# WikiPower.net
KiCad netlist of a schematic drawn in Altium Designer
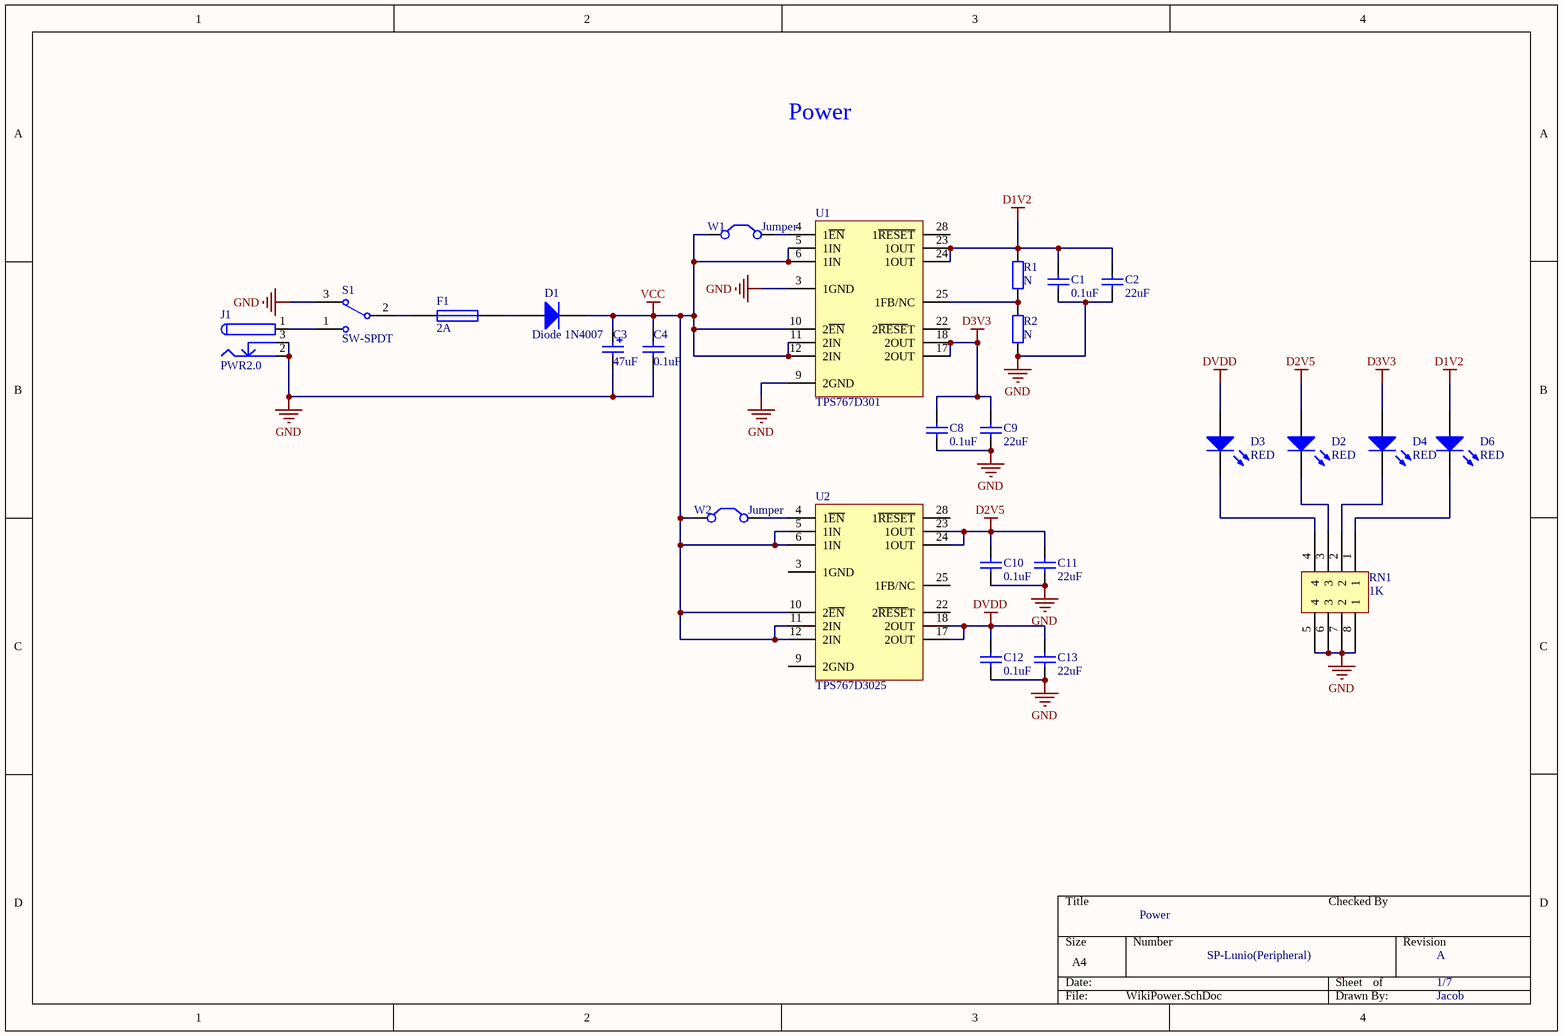
[diagram p0: WikiPower.SchDoc]

(export (version "E")
  (design (tool "Eeschema 10.0.6"))
  (components
    (comp (ref "C1")
      (value "0.1uF")
      (footprint "0603M")
      (description "Capacitor")
      (fields (field (name "PUBLISHER") "Altium Limited"))
      (libsource (lib "Miscellaneous Devices") (part "Cap"))
    )
    (comp (ref "C2")
      (value "22uF")
      (footprint "0805M")
      (description "Capacitor")
      (fields (field (name "PUBLISHER") "Altium Limited"))
      (libsource (lib "Miscellaneous Devices") (part "Cap"))
    )
    (comp (ref "C3")
      (value "47uF")
      (footprint "TAJ-A")
      (description "Polarized Capacitor (Radial)")
      (fields (field (name "PUBLISHER") "Altium Limited"))
      (libsource (lib "Studio") (part "Cap Pol1"))
    )
    (comp (ref "C4")
      (value "0.1uF")
      (footprint "0603M")
      (description "Capacitor")
      (fields (field (name "PUBLISHER") "Altium Limited"))
      (libsource (lib "Miscellaneous Devices") (part "Cap"))
    )
    (comp (ref "C8")
      (value "0.1uF")
      (footprint "0603M")
      (description "Capacitor")
      (fields (field (name "PUBLISHER") "Altium Limited"))
      (libsource (lib "Miscellaneous Devices") (part "Cap"))
    )
    (comp (ref "C9")
      (value "22uF")
      (footprint "0805M")
      (description "Capacitor")
      (fields (field (name "PUBLISHER") "Altium Limited"))
      (libsource (lib "Miscellaneous Devices") (part "Cap"))
    )
    (comp (ref "C10")
      (value "0.1uF")
      (footprint "0603M")
      (description "Capacitor")
      (fields (field (name "PUBLISHER") "Altium Limited"))
      (libsource (lib "Miscellaneous Devices") (part "Cap"))
    )
    (comp (ref "C11")
      (value "22uF")
      (footprint "0805M")
      (description "Capacitor")
      (fields (field (name "PUBLISHER") "Altium Limited"))
      (libsource (lib "Miscellaneous Devices") (part "Cap"))
    )
    (comp (ref "C12")
      (value "0.1uF")
      (footprint "0603M")
      (description "Capacitor")
      (fields (field (name "PUBLISHER") "Altium Limited"))
      (libsource (lib "Miscellaneous Devices") (part "Cap"))
    )
    (comp (ref "C13")
      (value "22uF")
      (footprint "0805M")
      (description "Capacitor")
      (fields (field (name "PUBLISHER") "Altium Limited"))
      (libsource (lib "Miscellaneous Devices") (part "Cap"))
    )
    (comp (ref "D1")
      (value "Diode 1N4007")
      (footprint "1210")
      (description "1 Amp General Purpose Rectifier")
      (fields (field (name "PUBLISHER") "Altium Limited"))
      (libsource (lib "Studio") (part "Diode 1N4007"))
    )
    (comp (ref "D2")
      (value "RED")
      (footprint "0603pn")
      (description "Typical INFRARED GaAs LED")
      (fields (field (name "PUBLISHER") "Altium Limited"))
      (libsource (lib "Miscellaneous Devices") (part "LED0"))
    )
    (comp (ref "D3")
      (value "RED")
      (footprint "0603pn")
      (description "Typical INFRARED GaAs LED")
      (fields (field (name "PUBLISHER") "Altium Limited"))
      (libsource (lib "Miscellaneous Devices") (part "LED0"))
    )
    (comp (ref "D4")
      (value "RED")
      (footprint "0603pn")
      (description "Typical INFRARED GaAs LED")
      (fields (field (name "PUBLISHER") "Altium Limited"))
      (libsource (lib "Miscellaneous Devices") (part "LED0"))
    )
    (comp (ref "D6")
      (value "RED")
      (footprint "0603pn")
      (description "Typical INFRARED GaAs LED")
      (fields (field (name "PUBLISHER") "Altium Limited"))
      (libsource (lib "Miscellaneous Devices") (part "LED0"))
    )
    (comp (ref "F1")
      (value "2A")
      (footprint "1210")
      (description "Fuse")
      (fields (field (name "PUBLISHER") "Altium Limited"))
      (libsource (lib "Studio") (part "Fuse 1"))
    )
    (comp (ref "J1")
      (value "PWR2.0")
      (footprint "PWR JACK 2.0MM")
      (description "Low Voltage Power Supply Connector")
      (fields (field (name "PUBLISHER") "Altium Limited"))
      (libsource (lib "Studio") (part "PWR2.5"))
    )
    (comp (ref "R1")
      (value "N")
      (footprint "0603M")
      (description "Resistor")
      (fields (field (name "PUBLISHER") "Altium Limited"))
      (libsource (lib "Miscellaneous Devices") (part "Res2"))
    )
    (comp (ref "R2")
      (value "N")
      (footprint "0603M")
      (description "Resistor")
      (fields (field (name "PUBLISHER") "Altium Limited"))
      (libsource (lib "Miscellaneous Devices") (part "Res2"))
    )
    (comp (ref "RN1")
      (value "1K")
      (footprint "RN1X4/0603")
      (description "Res Pack 2X4")
      (libsource (lib "Studio") (part "Res Pack 2X4"))
    )
    (comp (ref "S1")
      (value "SW-SPDT")
      (footprint "SK12D07VG3")
      (description "SPDT Subminiature Toggle Switch, Right Angle Mounting, Vertical Actuation")
      (fields (field (name "PUBLISHER") "Altium Limited"))
      (libsource (lib "Miscellaneous Devices") (part "SW-SPDT"))
    )
    (comp (ref "U1")
      (value "TPS767D301")
      (footprint "HTSSOP")
      (description "DOUBLE OUTPUT")
      (libsource (lib "Lunio") (part "TPS757D301"))
    )
    (comp (ref "U2")
      (value "TPS767D3025")
      (footprint "HTSSOP")
      (description "DUAL-OUTPUT LOW-DROPOUT VOLTAGE REGULATORS")
      (libsource (lib "Studio") (part "TPS757D3XX"))
    )
    (comp (ref "W1")
      (value "Jumper")
      (footprint "HDR1X2/2.00MM")
      (description "Jumper Wire")
      (fields (field (name "PUBLISHER") "Altium Limited"))
      (libsource (lib "Miscellaneous Devices") (part "Jumper"))
    )
    (comp (ref "W2")
      (value "Jumper")
      (footprint "HDR1X2/2.00MM")
      (description "Jumper Wire")
      (fields (field (name "PUBLISHER") "Altium Limited"))
      (libsource (lib "Miscellaneous Devices") (part "Jumper"))
    )
  )
  (nets
    (net (code "1") (name "D1V2") (class "Default")
      (node (ref "C1") (pin "2") (pinfunction "2_2") (pintype "passive"))
      (node (ref "C2") (pin "2") (pinfunction "2_2") (pintype "passive"))
      (node (ref "D6") (pin "1") (pinfunction "A_1") (pintype "passive"))
      (node (ref "R1") (pin "2") (pinfunction "2_2") (pintype "passive"))
      (node (ref "U1") (pin "23") (pinfunction "1OUT_23") (pintype "power_in"))
      (node (ref "U1") (pin "24") (pinfunction "1OUT_24") (pintype "power_in"))
    )
    (net (code "2") (name "D2V5") (class "Default")
      (node (ref "C10") (pin "2") (pinfunction "2_2") (pintype "passive"))
      (node (ref "C11") (pin "2") (pinfunction "2_2") (pintype "passive"))
      (node (ref "D2") (pin "1") (pinfunction "A_1") (pintype "passive"))
      (node (ref "U2") (pin "23") (pinfunction "1OUT_23") (pintype "power_in"))
      (node (ref "U2") (pin "24") (pinfunction "1OUT_24") (pintype "power_in"))
    )
    (net (code "3") (name "D3V3") (class "Default")
      (node (ref "C8") (pin "2") (pinfunction "2_2") (pintype "passive"))
      (node (ref "C9") (pin "2") (pinfunction "2_2") (pintype "passive"))
      (node (ref "D4") (pin "1") (pinfunction "A_1") (pintype "passive"))
      (node (ref "U1") (pin "17") (pinfunction "2OUT_17") (pintype "power_in"))
      (node (ref "U1") (pin "18") (pinfunction "2OUT_18") (pintype "power_in"))
    )
    (net (code "4") (name "DVDD") (class "Default")
      (node (ref "C12") (pin "2") (pinfunction "2_2") (pintype "passive"))
      (node (ref "C13") (pin "2") (pinfunction "2_2") (pintype "passive"))
      (node (ref "D3") (pin "1") (pinfunction "A_1") (pintype "passive"))
      (node (ref "U2") (pin "17") (pinfunction "2OUT_17") (pintype "power_in"))
      (node (ref "U2") (pin "18") (pinfunction "2OUT_18") (pintype "power_in"))
    )
    (net (code "5") (name "GND") (class "Default")
      (node (ref "C1") (pin "1") (pinfunction "1_1") (pintype "passive"))
      (node (ref "C10") (pin "1") (pinfunction "1_1") (pintype "passive"))
      (node (ref "C11") (pin "1") (pinfunction "1_1") (pintype "passive"))
      (node (ref "C12") (pin "1") (pinfunction "1_1") (pintype "passive"))
      (node (ref "C13") (pin "1") (pinfunction "1_1") (pintype "passive"))
      (node (ref "C2") (pin "1") (pinfunction "1_1") (pintype "passive"))
      (node (ref "C3") (pin "2") (pinfunction "2_2") (pintype "passive"))
      (node (ref "C4") (pin "1") (pinfunction "1_1") (pintype "passive"))
      (node (ref "C8") (pin "1") (pinfunction "1_1") (pintype "passive"))
      (node (ref "C9") (pin "1") (pinfunction "1_1") (pintype "passive"))
      (node (ref "J1") (pin "2") (pinfunction "2_2") (pintype "power_in"))
      (node (ref "J1") (pin "3") (pinfunction "3_3") (pintype "power_in"))
      (node (ref "R2") (pin "1") (pinfunction "1_1") (pintype "passive"))
      (node (ref "RN1") (pin "5") (pinfunction "4_5") (pintype "passive"))
      (node (ref "RN1") (pin "6") (pinfunction "3_6") (pintype "passive"))
      (node (ref "RN1") (pin "7") (pinfunction "2_7") (pintype "passive"))
      (node (ref "RN1") (pin "8") (pinfunction "1_8") (pintype "passive"))
      (node (ref "S1") (pin "3") (pinfunction "3_3") (pintype "passive"))
      (node (ref "U1") (pin "3") (pinfunction "1GND_3") (pintype "power_in"))
      (node (ref "U1") (pin "9") (pinfunction "2GND_9") (pintype "power_in"))
    )
    (net (code "6") (name "Net-(D1-A)") (class "Default")
      (node (ref "D1") (pin "1") (pinfunction "A_1") (pintype "passive"))
      (node (ref "F1") (pin "2") (pinfunction "2_2") (pintype "passive"))
    )
    (net (code "7") (name "Net-(D2-K)") (class "Default")
      (node (ref "D2") (pin "2") (pinfunction "K_2") (pintype "passive"))
      (node (ref "RN1") (pin "3") (pinfunction "3_3") (pintype "passive"))
    )
    (net (code "8") (name "Net-(D3-K)") (class "Default")
      (node (ref "D3") (pin "2") (pinfunction "K_2") (pintype "passive"))
      (node (ref "RN1") (pin "4") (pinfunction "4_4") (pintype "passive"))
    )
    (net (code "9") (name "Net-(D4-K)") (class "Default")
      (node (ref "D4") (pin "2") (pinfunction "K_2") (pintype "passive"))
      (node (ref "RN1") (pin "2") (pinfunction "2_2") (pintype "passive"))
    )
    (net (code "10") (name "Net-(D6-K)") (class "Default")
      (node (ref "D6") (pin "2") (pinfunction "K_2") (pintype "passive"))
      (node (ref "RN1") (pin "1") (pinfunction "1_1") (pintype "passive"))
    )
    (net (code "11") (name "Net-(F1-Pad1)") (class "Default")
      (node (ref "F1") (pin "1") (pinfunction "1_1") (pintype "passive"))
      (node (ref "S1") (pin "2") (pinfunction "2_2") (pintype "passive"))
    )
    (net (code "12") (name "Net-(J1-Pad1)") (class "Default")
      (node (ref "J1") (pin "1") (pinfunction "1_1") (pintype "power_in"))
      (node (ref "S1") (pin "1") (pinfunction "1_1") (pintype "passive"))
    )
    (net (code "13") (name "Net-(U1-1FB{slash}NC)") (class "Default")
      (node (ref "R1") (pin "1") (pinfunction "1_1") (pintype "passive"))
      (node (ref "R2") (pin "2") (pinfunction "2_2") (pintype "passive"))
      (node (ref "U1") (pin "25") (pinfunction "1FB/NC_25") (pintype "power_in"))
    )
    (net (code "14") (name "Net-(U1-1~{EN})") (class "Default")
      (node (ref "U1") (pin "4") (pinfunction "1~{EN}_4") (pintype "power_in"))
      (node (ref "W1") (pin "2") (pinfunction "C2_2") (pintype "passive"))
    )
    (net (code "15") (name "Net-(U2-1~{EN})") (class "Default")
      (node (ref "U2") (pin "4") (pinfunction "1~{EN}_4") (pintype "power_in"))
      (node (ref "W2") (pin "2") (pinfunction "C2_2") (pintype "passive"))
    )
    (net (code "16") (name "VCC") (class "Default")
      (node (ref "C3") (pin "1") (pinfunction "1_1") (pintype "passive"))
      (node (ref "C4") (pin "2") (pinfunction "2_2") (pintype "passive"))
      (node (ref "D1") (pin "2") (pinfunction "K_2") (pintype "passive"))
      (node (ref "U1") (pin "10") (pinfunction "2~{EN}_10") (pintype "power_in"))
      (node (ref "U1") (pin "11") (pinfunction "2IN_11") (pintype "power_in"))
      (node (ref "U1") (pin "12") (pinfunction "2IN_12") (pintype "power_in"))
      (node (ref "U1") (pin "5") (pinfunction "1IN_5") (pintype "power_in"))
      (node (ref "U1") (pin "6") (pinfunction "1IN_6") (pintype "power_in"))
      (node (ref "U2") (pin "10") (pinfunction "2~{EN}_10") (pintype "power_in"))
      (node (ref "U2") (pin "11") (pinfunction "2IN_11") (pintype "power_in"))
      (node (ref "U2") (pin "12") (pinfunction "2IN_12") (pintype "power_in"))
      (node (ref "U2") (pin "5") (pinfunction "1IN_5") (pintype "power_in"))
      (node (ref "U2") (pin "6") (pinfunction "1IN_6") (pintype "power_in"))
      (node (ref "W1") (pin "1") (pinfunction "C1_1") (pintype "passive"))
      (node (ref "W2") (pin "1") (pinfunction "C1_1") (pintype "passive"))
    )
    (net (code "17") (name "unconnected-(U1-1~{RESET}-Pad28)") (class "Default")
      (node (ref "U1") (pin "28") (pinfunction "1~{RESET}_28") (pintype "power_in"))
    )
    (net (code "18") (name "unconnected-(U1-2~{RESE}T-Pad22)") (class "Default")
      (node (ref "U1") (pin "22") (pinfunction "2~{RESE}T_22") (pintype "power_in"))
    )
    (net (code "19") (name "unconnected-(U2-1FB{slash}NC-Pad25)") (class "Default")
      (node (ref "U2") (pin "25") (pinfunction "1FB/NC_25") (pintype "power_in"))
    )
    (net (code "20") (name "unconnected-(U2-1GND-Pad3)") (class "Default")
      (node (ref "U2") (pin "3") (pinfunction "1GND_3") (pintype "power_in"))
    )
    (net (code "21") (name "unconnected-(U2-1~{RESET}-Pad28)") (class "Default")
      (node (ref "U2") (pin "28") (pinfunction "1~{RESET}_28") (pintype "power_in"))
    )
    (net (code "22") (name "unconnected-(U2-2GND-Pad9)") (class "Default")
      (node (ref "U2") (pin "9") (pinfunction "2GND_9") (pintype "power_in"))
    )
    (net (code "23") (name "unconnected-(U2-2~{RESE}T-Pad22)") (class "Default")
      (node (ref "U2") (pin "22") (pinfunction "2~{RESE}T_22") (pintype "power_in"))
    )
  )
)
